# Power_USB.net
KiCad netlist of a schematic drawn in Altium Designer
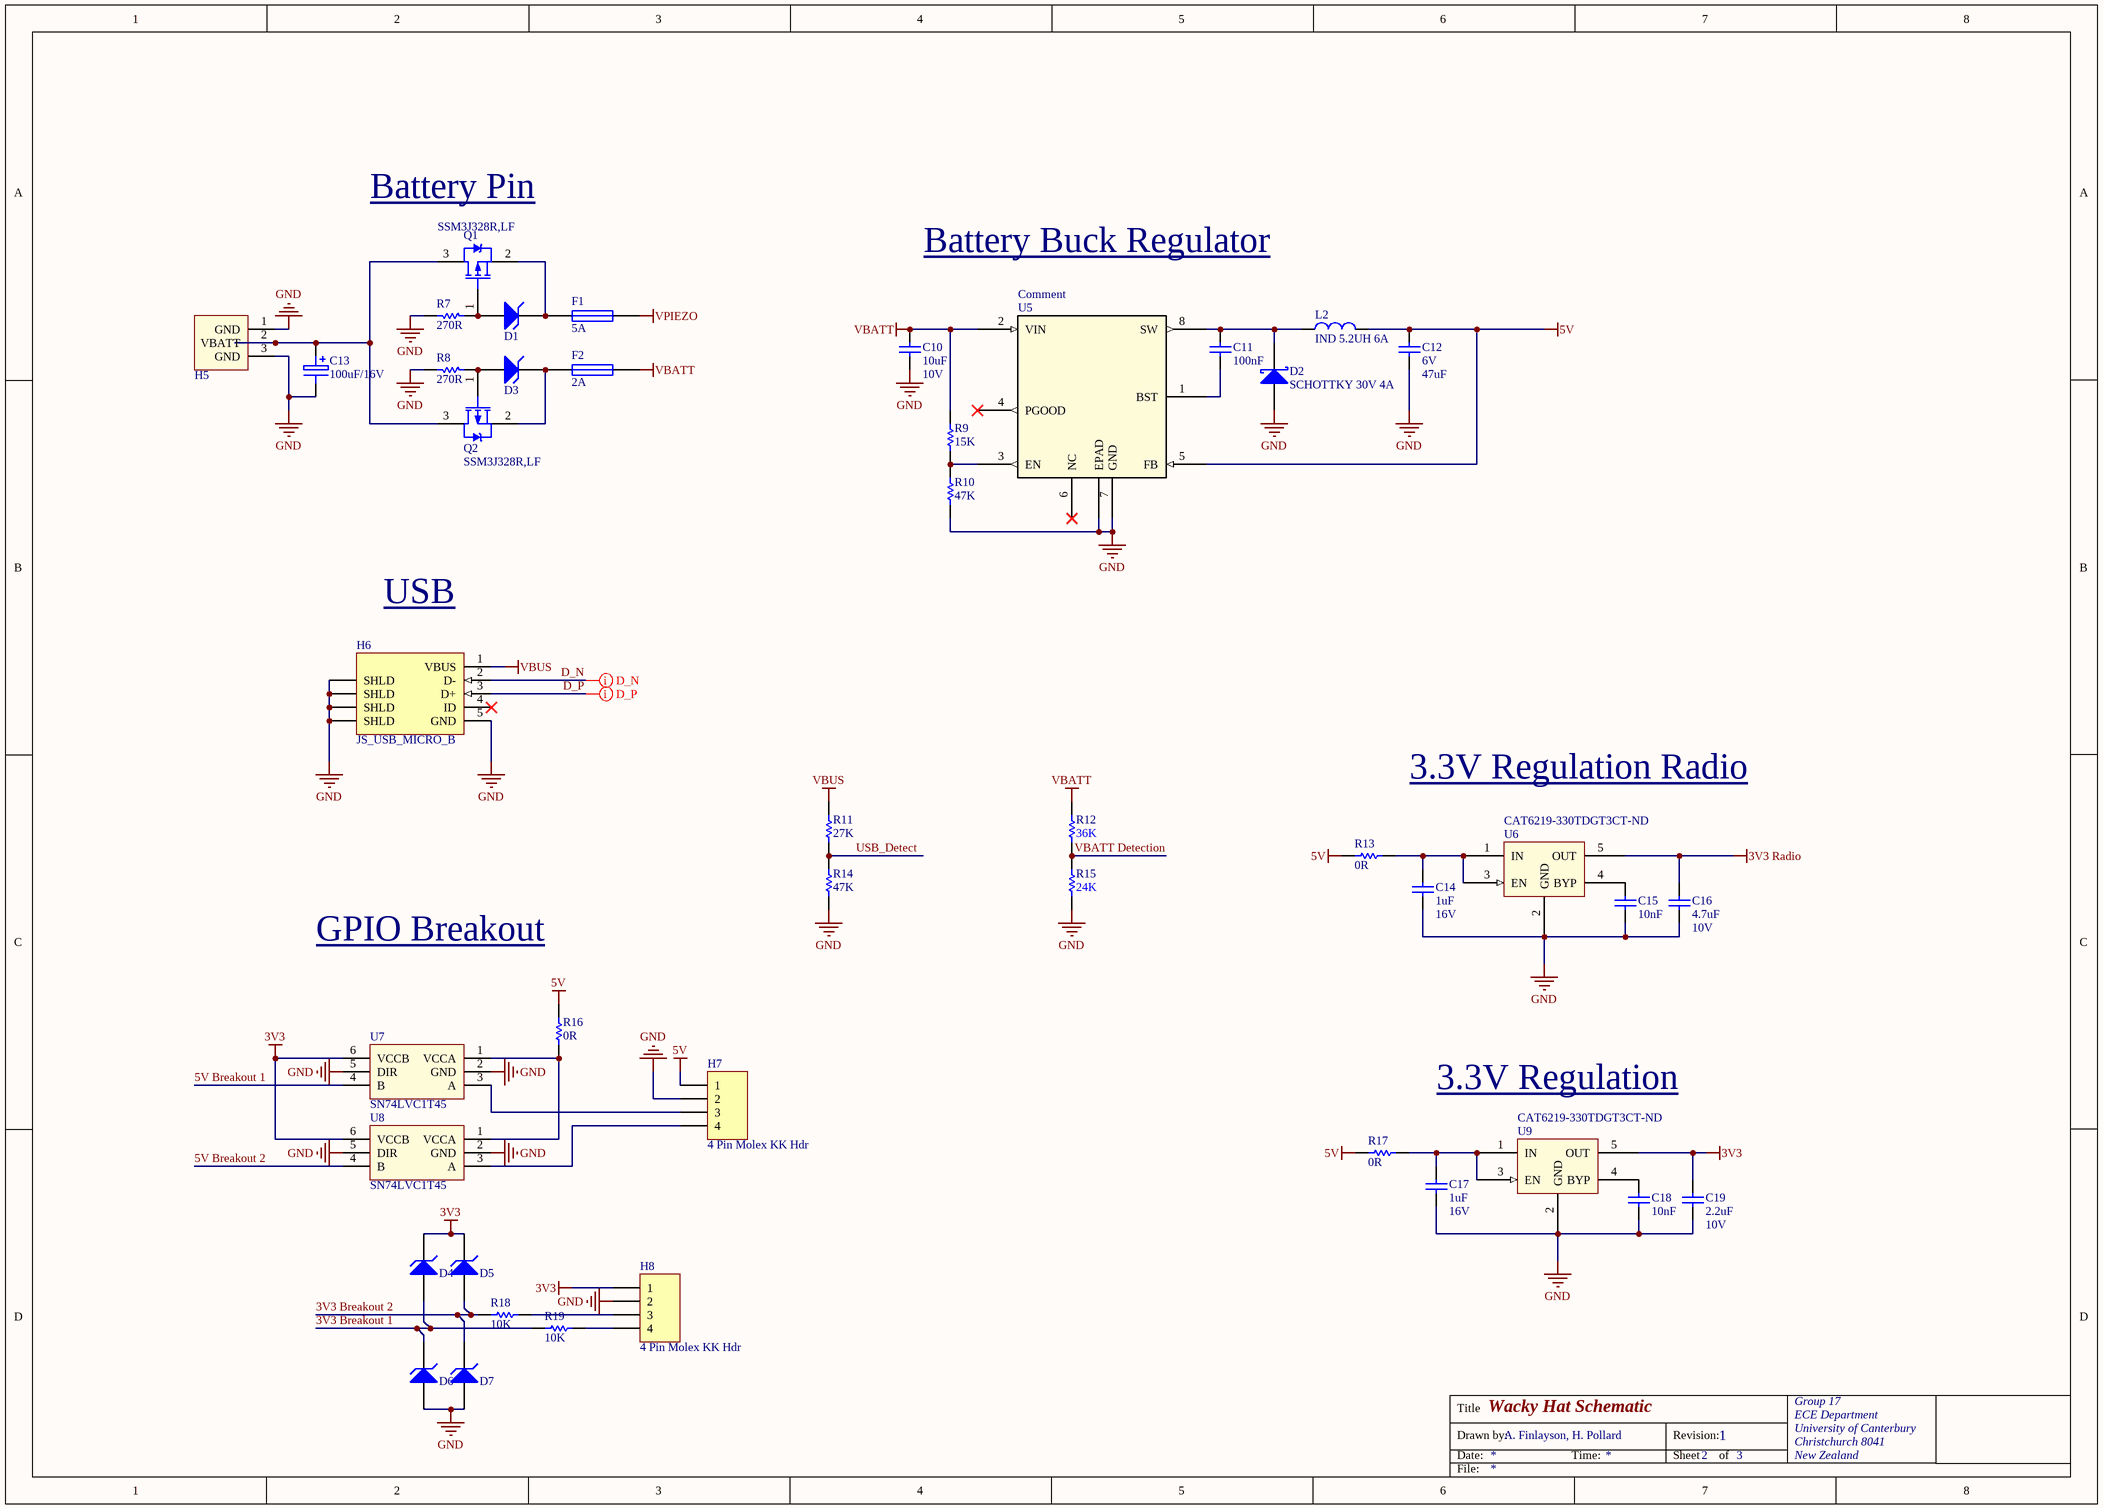
[diagram p0: Power_USB.SchDoc]

(export (version "E")
  (design (tool "Eeschema 10.0.6"))
  (components
    (comp (ref "C10")
      (value "10uF")
      (footprint "CAPC2012L")
      (description "CAP CER 10uF X7R +-20% 10V 0805")
      (fields (field (name "MAX VOLTAGE") "10V"))
      (libsource (lib "ECE AD19Components_19V1") (part "CC_10uF_0805_10V"))
    )
    (comp (ref "C11")
      (value "100nF")
      (footprint "CAPC1608L")
      (description "CAP CER 100nF X7R +-10% 50V 0603")
      (libsource (lib "ECE AD19Components_19V1") (part "CC_100nF_0603"))
    )
    (comp (ref "C12")
      (value "47uF")
      (footprint "CAPC3216L")
      (description "CAP CER 47uF X5R -/+20% 6V 1206")
      (fields (field (name "MAX VOLTAGE") "6V"))
      (libsource (lib "ECE AD19Components_19V1") (part "CC_47uF_1206"))
    )
    (comp (ref "C13")
      (value "100uF/16V")
      (footprint "NICH-1")
      (description "CAP ALUM 100uF 16V SMD")
      (fields (field (name "MANUFACTURER") "Nichcon"))
      (libsource (lib "ECE AD19Components_19V1") (part "CA_100uF_16V"))
    )
    (comp (ref "C14")
      (value "1uF")
      (footprint "CAPC1608L")
      (description "CAP CER 1uF Y5V -20% +80% 16V 0603")
      (fields (field (name "MAX VOLTAGE") "16V"))
      (libsource (lib "ECE AD19Components_19V1") (part "CC_1uF_0603"))
    )
    (comp (ref "C15")
      (value "10nF")
      (footprint "CAPC1608L")
      (description "CAP CER 10nF X7R +-10% 50V 0603")
      (libsource (lib "ECE AD19Components_19V1") (part "CC_10nF_0603"))
    )
    (comp (ref "C16")
      (value "4.7uF")
      (footprint "CAPC1608N")
      (description "CAP CER 4.7uF X5R +-20%  10V 0603")
      (fields (field (name "MAX VOLTAGE") "10V"))
      (libsource (lib "ECE AD19Components_19V1") (part "CC_4.7uF_0603"))
    )
    (comp (ref "C17")
      (value "1uF")
      (footprint "CAPC1608L")
      (description "CAP CER 1uF Y5V -20% +80% 16V 0603")
      (fields (field (name "MAX VOLTAGE") "16V"))
      (libsource (lib "ECE AD19Components_19V1") (part "CC_1uF_0603"))
    )
    (comp (ref "C18")
      (value "10nF")
      (footprint "CAPC1608L")
      (description "CAP CER 10nF X7R +-10% 50V 0603")
      (libsource (lib "ECE AD19Components_19V1") (part "CC_10nF_0603"))
    )
    (comp (ref "C19")
      (value "2.2uF")
      (footprint "CAPC1608L")
      (description "CAP CER 2.2uF X5R +-20% 10V 0603")
      (fields (field (name "MAX VOLTAGE") "10V"))
      (libsource (lib "ECE AD19Components_19V1") (part "CC_2.2uF_0603"))
    )
    (comp (ref "D1")
      (value "DIODE ZENER 5.6V")
      (footprint "DO-214AA_SCL")
      (description "DIODE ZENER 5.6V 5W DO214AA")
      (fields
        (field (name "MANUFACTURER") "Micro Commercial Co")
        (field (name "MANUFACTURER PART NUMBER") "SMBJ5339B-TP")
      )
      (libsource (lib "ENCE461AD19_19V2") (part "SMBJ5339B-TP"))
    )
    (comp (ref "D2")
      (value "SCHOTTKY 30V 4A")
      (footprint "SMC")
      (description "DIODE SCHOTTKY 30V 4A SMC")
      (fields
        (field (name "MANUFACTURER") "ON Semiconductor")
        (field (name "MANUFACTURER PART NUMBER") "MBRS330T3G")
      )
      (libsource (lib "ENCE461AD19_19V2") (part "MBRS330T3G"))
    )
    (comp (ref "D3")
      (value "DIODE ZENER 5.6V")
      (footprint "DO-214AA_SCL")
      (description "DIODE ZENER 5.6V 5W DO214AA")
      (fields
        (field (name "MANUFACTURER") "Micro Commercial Co")
        (field (name "MANUFACTURER PART NUMBER") "SMBJ5339B-TP")
      )
      (libsource (lib "ENCE461AD19_19V2") (part "SMBJ5339B-TP"))
    )
    (comp (ref "D4")
      (value "DIODE ZENER 5.6V")
      (footprint "DO-214AA_SCL")
      (description "DIODE ZENER 5.6V 5W DO214AA")
      (fields
        (field (name "MANUFACTURER") "Micro Commercial Co")
        (field (name "MANUFACTURER PART NUMBER") "SMBJ5339B-TP")
      )
      (libsource (lib "ENCE461AD19_19V2") (part "SMBJ5339B-TP"))
    )
    (comp (ref "D5")
      (value "DIODE ZENER 5.6V")
      (footprint "DO-214AA_SCL")
      (description "DIODE ZENER 5.6V 5W DO214AA")
      (fields
        (field (name "MANUFACTURER") "Micro Commercial Co")
        (field (name "MANUFACTURER PART NUMBER") "SMBJ5339B-TP")
      )
      (libsource (lib "ENCE461AD19_19V2") (part "SMBJ5339B-TP"))
    )
    (comp (ref "D6")
      (value "DIODE ZENER 5.6V")
      (footprint "DO-214AA_SCL")
      (description "DIODE ZENER 5.6V 5W DO214AA")
      (fields
        (field (name "MANUFACTURER") "Micro Commercial Co")
        (field (name "MANUFACTURER PART NUMBER") "SMBJ5339B-TP")
      )
      (libsource (lib "ENCE461AD19_19V2") (part "SMBJ5339B-TP"))
    )
    (comp (ref "D7")
      (value "DIODE ZENER 5.6V")
      (footprint "DO-214AA_SCL")
      (description "DIODE ZENER 5.6V 5W DO214AA")
      (fields
        (field (name "MANUFACTURER") "Micro Commercial Co")
        (field (name "MANUFACTURER PART NUMBER") "SMBJ5339B-TP")
      )
      (libsource (lib "ENCE461AD19_19V2") (part "SMBJ5339B-TP"))
    )
    (comp (ref "F1")
      (value "5A")
      (footprint "RESC3216N")
      (description "Fuse 5.0A Fast Acting 1206 SMD")
      (fields (field (name "MANUFACTURER PART NUMBER") "C1F5") (field (name "MANUFACTURER") "Bel TRP"))
      (libsource (lib "ECE AD19Components_19V1") (part "FS_Fuse_5.0A"))
    )
    (comp (ref "F2")
      (value "2A")
      (footprint "RESC3216N")
      (description "Fuse 2.0A Very Fast Acting 1206 SMD")
      (fields
        (field (name "MANUFACTURER") "MULTICOMP")
        (field (name "MANUFACTURER PART NUMBER") "MC12CF 002")
      )
      (libsource (lib "ECE AD19Components_19V1") (part "FS_Fuse_2.0A"))
    )
    (comp (ref "H5")
      (value "Battery_HEADER_3pin")
      (footprint "BATT_HEADER_3POS")
      (description "3Pin Header 2.54mm spacing")
      (libsource (lib "ENCE461AD19_19V2") (part "Battery_HEADER_3pin"))
    )
    (comp (ref "H6")
      (value "JS_USB_MICRO_B")
      (footprint "FCI_USB_10118194-0001LF")
      (description "CONN USB MICRO B RECPT SMT R/A")
      (fields (field (name "MANUFACTURER") "FCI") (field (name "MANUFACTURER PART NUMBER") "10118194-0001LF"))
      (libsource (lib "ECE AD19Components_19V1") (part "JS_USB_MICRO_B_SMT"))
    )
    (comp (ref "H7")
      (value "4 Pin Molex KK Hdr")
      (footprint "MOLEX_KK_4_HDR")
      (description "CONN HEADER 4POS 2.54mm VERT_Thru Hole")
      (fields (field (name "MANUFACTURER") "Molex"))
      (libsource (lib "ECE AD19Components_19V1") (part "JA_MOLEX_KK_4POS"))
    )
    (comp (ref "H8")
      (value "4 Pin Molex KK Hdr")
      (footprint "MOLEX_KK_4_HDR")
      (description "CONN HEADER 4POS 2.54mm VERT_Thru Hole")
      (fields (field (name "MANUFACTURER") "Molex"))
      (libsource (lib "ECE AD19Components_19V1") (part "JA_MOLEX_KK_4POS"))
    )
    (comp (ref "L2")
      (value "IND 5.2UH 6A")
      (footprint "INDUCTOR5u2")
      (description "FIXED IND 5.2UH 6A 22 MOHM SMD")
      (fields
        (field (name "MANUFACTURER") "Sumida America Components Inc.")
        (field (name "MANUFACTURER PART NUMBER") "CDRH104RNP-5R2NC")
      )
      (libsource (lib "ENCE461AD19_19V2") (part "CDRH104RNP-5R2NC"))
    )
    (comp (ref "Q1")
      (value "SSM3J328R,LF")
      (footprint "SOT23_L")
      (description "MOSFET P-CH 20V 6A SOT23-3")
      (fields
        (field (name "MANUFACTURER") "Toshiba")
        (field (name "MANUFACTURER PART NUMBER") "SSM3J328R,LF")
      )
      (libsource (lib "ECE AD19Components_19V1") (part "TM_SSM3J328R"))
    )
    (comp (ref "Q2")
      (value "SSM3J328R,LF")
      (footprint "SOT23_L")
      (description "MOSFET P-CH 20V 6A SOT23-3")
      (fields
        (field (name "MANUFACTURER") "Toshiba")
        (field (name "MANUFACTURER PART NUMBER") "SSM3J328R,LF")
      )
      (libsource (lib "ECE AD19Components_19V1") (part "TM_SSM3J328R"))
    )
    (comp (ref "R7")
      (value "270R")
      (footprint "RESC1608L")
      (description "RES 270 OHM 1/10W 5% 0603 SMD")
      (libsource (lib "ECE AD19Components_19V1") (part "RS_270R"))
    )
    (comp (ref "R8")
      (value "270R")
      (footprint "RESC1608L")
      (description "RES 270 OHM 1/10W 5% 0603 SMD")
      (libsource (lib "ECE AD19Components_19V1") (part "RS_270R"))
    )
    (comp (ref "R9")
      (value "15K")
      (footprint "RESC1608L")
      (description "RES 15.0K OHM 1/10W 5% 0603 SMD")
      (libsource (lib "ECE AD19Components_19V1") (part "RS_15K"))
    )
    (comp (ref "R10")
      (value "47K")
      (footprint "RESC1608N")
      (description "RES 47.0K OHM 1/10W 5% 0603 SMD")
      (libsource (lib "ECE AD19Components_19V1") (part "RS_47K"))
    )
    (comp (ref "R11")
      (value "27K")
      (footprint "RESC1608L")
      (description "RES 27K OHM 1/10W 5% 0603 SMD")
      (libsource (lib "ECE AD19Components_19V1") (part "RS_27K"))
    )
    (comp (ref "R12")
      (value "36K")
      (footprint "RESC1608L")
      (description "RES 36K OHM 1/10W 5% 0603 SMD")
      (libsource (lib "ECE AD19Components_19V1") (part "RS_36K"))
    )
    (comp (ref "R13")
      (value "0R")
      (footprint "RESC1608L")
      (description "RES 0.0 OHM 1/10W 5% 0603 SMD")
      (libsource (lib "ECE AD19Components_19V1") (part "RS_0R0"))
    )
    (comp (ref "R14")
      (value "47K")
      (footprint "RESC1608L")
      (description "RES 47.0K OHM 1/10W 5% 0603 SMD")
      (libsource (lib "ECE AD19Components_19V1") (part "RS_47K"))
    )
    (comp (ref "R15")
      (value "24K")
      (footprint "RESC1608L")
      (description "RES 24K OHM 1/10W 5% 0603 SMD")
      (libsource (lib "ECE AD19Components_19V1") (part "RS_24K"))
    )
    (comp (ref "R16")
      (value "0R")
      (footprint "RESC1608L")
      (description "RES 0.0 OHM 1/10W 5% 0603 SMD")
      (libsource (lib "ECE AD19Components_19V1") (part "RS_0R0"))
    )
    (comp (ref "R17")
      (value "0R")
      (footprint "RESC1608L")
      (description "RES 0.0 OHM 1/10W 5% 0603 SMD")
      (libsource (lib "ECE AD19Components_19V1") (part "RS_0R0"))
    )
    (comp (ref "R18")
      (value "10K")
      (footprint "RESC1608L")
      (description "RES 10.0K OHM 1/10W 5% 0603 SMD")
      (libsource (lib "ECE AD19Components_19V1") (part "RS_10K"))
    )
    (comp (ref "R19")
      (value "10K")
      (footprint "RESC1608L")
      (description "RES 10.0K OHM 1/10W 5% 0603 SMD")
      (libsource (lib "ECE AD19Components_19V1") (part "RS_10K"))
    )
    (comp (ref "U5")
      (value "Comment")
      (footprint "RD_8_1")
      (description "IC REG BUCK 5V 2A 8SOIC")
      (fields (field (name "MANUFACTURER_PART_NUMBER") "ADP2302ARDZ-5.0-R7"))
      (libsource (lib "ENCE461AD19_19V2") (part "ADP2302ARDZ-5.0-R7"))
    )
    (comp (ref "U6")
      (value "CAT6219-330TDGT3")
      (footprint "SOT95P280X145-5N")
      (description "IC REG LIN 3.3V 500MA TSOT23-5")
      (fields
        (field (name "BASE PART NUMBER") "CAT6219")
        (field (name "SUPPLIER PART NUMBER") "CAT6219-330TDGT3CT-ND")
      )
      (libsource (lib "ENCE461AD19_19V2") (part "SV_CAT6219-330TDGT3"))
    )
    (comp (ref "U7")
      (value "SN74LVC1T45")
      (footprint "SOT23-6_N")
      (description "1.8V - 5V level converter")
      (libsource (lib "ENCE461_extras_2020") (part "SN74LVC1T45"))
    )
    (comp (ref "U8")
      (value "SN74LVC1T45")
      (footprint "SOT23-6_N")
      (description "1.8V - 5V level converter")
      (libsource (lib "ENCE461_extras_2020") (part "SN74LVC1T45"))
    )
    (comp (ref "U9")
      (value "CAT6219-330TDGT3")
      (footprint "SOT95P280X145-5N")
      (description "IC REG LIN 3.3V 500MA TSOT23-5")
      (fields
        (field (name "BASE PART NUMBER") "CAT6219")
        (field (name "SUPPLIER PART NUMBER") "CAT6219-330TDGT3CT-ND")
      )
      (libsource (lib "ENCE461AD19_19V2") (part "SV_CAT6219-330TDGT3"))
    )
  )
  (nets
    (net (code "1") (name "/3V3 Breakout 1") (class "Default")
      (node (ref "D4") (pin "2") (pinfunction "A_2") (pintype "passive"))
      (node (ref "D6") (pin "1") (pinfunction "K_1") (pintype "passive"))
      (node (ref "R19") (pin "1") (pinfunction "1_1") (pintype "passive"))
    )
    (net (code "2") (name "/3V3 Breakout 2") (class "Default")
      (node (ref "D5") (pin "2") (pinfunction "A_2") (pintype "passive"))
      (node (ref "D7") (pin "1") (pinfunction "K_1") (pintype "passive"))
      (node (ref "R18") (pin "1") (pinfunction "1_1") (pintype "passive"))
    )
    (net (code "3") (name "/5V Breakout 1") (class "Default")
      (node (ref "U7") (pin "4") (pinfunction "B_4") (pintype "passive"))
    )
    (net (code "4") (name "/5V Breakout 2") (class "Default")
      (node (ref "U8") (pin "4") (pinfunction "B_4") (pintype "passive"))
    )
    (net (code "5") (name "/D_N") (class "Default")
      (node (ref "H6") (pin "2") (pinfunction "D-_2") (pintype "input"))
    )
    (net (code "6") (name "/D_P") (class "Default")
      (node (ref "H6") (pin "3") (pinfunction "D+_3") (pintype "input"))
    )
    (net (code "7") (name "/USB_Detect") (class "Default")
      (node (ref "R11") (pin "1") (pinfunction "1_1") (pintype "passive"))
      (node (ref "R14") (pin "2") (pinfunction "2_2") (pintype "passive"))
    )
    (net (code "8") (name "/VBATT Detection") (class "Default")
      (node (ref "R12") (pin "1") (pinfunction "1_1") (pintype "passive"))
      (node (ref "R15") (pin "2") (pinfunction "2_2") (pintype "passive"))
    )
    (net (code "9") (name "3V3") (class "Default")
      (node (ref "C19") (pin "2") (pinfunction "2_2") (pintype "passive"))
      (node (ref "D4") (pin "1") (pinfunction "K_1") (pintype "passive"))
      (node (ref "D5") (pin "1") (pinfunction "K_1") (pintype "passive"))
      (node (ref "H8") (pin "1") (pinfunction "1_1") (pintype "passive"))
      (node (ref "U7") (pin "6") (pinfunction "VCCB_6") (pintype "passive"))
      (node (ref "U8") (pin "6") (pinfunction "VCCB_6") (pintype "passive"))
      (node (ref "U9") (pin "5") (pinfunction "OUT_5") (pintype "power_in"))
    )
    (net (code "10") (name "3V3 Radio") (class "Default")
      (node (ref "C16") (pin "2") (pinfunction "2_2") (pintype "passive"))
      (node (ref "U6") (pin "5") (pinfunction "OUT_5") (pintype "power_in"))
    )
    (net (code "11") (name "5V") (class "Default")
      (node (ref "C12") (pin "2") (pinfunction "2_2") (pintype "passive"))
      (node (ref "H7") (pin "1") (pinfunction "1_1") (pintype "passive"))
      (node (ref "L2") (pin "2") (pintype "passive"))
      (node (ref "R13") (pin "1") (pinfunction "1_1") (pintype "passive"))
      (node (ref "R16") (pin "2") (pinfunction "2_2") (pintype "passive"))
      (node (ref "R17") (pin "1") (pinfunction "1_1") (pintype "passive"))
      (node (ref "U5") (pin "5") (pinfunction "FB_5") (pintype "input"))
    )
    (net (code "12") (name "GND") (class "Default")
      (node (ref "C10") (pin "1") (pinfunction "1_1") (pintype "passive"))
      (node (ref "C12") (pin "1") (pinfunction "1_1") (pintype "passive"))
      (node (ref "C13") (pin "1") (pintype "passive"))
      (node (ref "C14") (pin "1") (pinfunction "1_1") (pintype "passive"))
      (node (ref "C15") (pin "1") (pinfunction "1_1") (pintype "passive"))
      (node (ref "C16") (pin "1") (pinfunction "1_1") (pintype "passive"))
      (node (ref "C17") (pin "1") (pinfunction "1_1") (pintype "passive"))
      (node (ref "C18") (pin "1") (pinfunction "1_1") (pintype "passive"))
      (node (ref "C19") (pin "1") (pinfunction "1_1") (pintype "passive"))
      (node (ref "D2") (pin "1") (pinfunction "A_1") (pintype "passive"))
      (node (ref "D6") (pin "2") (pinfunction "A_2") (pintype "passive"))
      (node (ref "D7") (pin "2") (pinfunction "A_2") (pintype "passive"))
      (node (ref "H5") (pin "1") (pinfunction "GND_1") (pintype "passive"))
      (node (ref "H5") (pin "3") (pinfunction "GND_3") (pintype "passive"))
      (node (ref "H6") (pin "5") (pinfunction "GND_5") (pintype "passive"))
      (node (ref "H6") (pin "6") (pinfunction "SHLD_6") (pintype "passive"))
      (node (ref "H7") (pin "2") (pinfunction "2_2") (pintype "passive"))
      (node (ref "H8") (pin "2") (pinfunction "2_2") (pintype "passive"))
      (node (ref "R10") (pin "1") (pinfunction "1_1") (pintype "passive"))
      (node (ref "R14") (pin "1") (pinfunction "1_1") (pintype "passive"))
      (node (ref "R15") (pin "1") (pinfunction "1_1") (pintype "passive"))
      (node (ref "R7") (pin "1") (pinfunction "1_1") (pintype "passive"))
      (node (ref "R8") (pin "1") (pinfunction "1_1") (pintype "passive"))
      (node (ref "U5") (pin "7") (pinfunction "GND_7") (pintype "power_in"))
      (node (ref "U5") (pin "EPAD") (pinfunction "EPAD_EPAD") (pintype "passive"))
      (node (ref "U6") (pin "2") (pinfunction "GND_2") (pintype "power_in"))
      (node (ref "U7") (pin "2") (pinfunction "GND_2") (pintype "passive"))
      (node (ref "U7") (pin "5") (pinfunction "DIR_5") (pintype "passive"))
      (node (ref "U8") (pin "2") (pinfunction "GND_2") (pintype "passive"))
      (node (ref "U8") (pin "5") (pinfunction "DIR_5") (pintype "passive"))
      (node (ref "U9") (pin "2") (pinfunction "GND_2") (pintype "power_in"))
    )
    (net (code "13") (name "Net-(D1-A)") (class "Default")
      (node (ref "D1") (pin "2") (pinfunction "A_2") (pintype "passive"))
      (node (ref "Q1") (pin "1") (pinfunction "1_1") (pintype "passive"))
      (node (ref "R7") (pin "2") (pinfunction "2_2") (pintype "passive"))
    )
    (net (code "14") (name "Net-(D1-K)") (class "Default")
      (node (ref "D1") (pin "1") (pinfunction "K_1") (pintype "passive"))
      (node (ref "F1") (pin "1") (pinfunction "1_1") (pintype "passive"))
      (node (ref "Q1") (pin "2") (pinfunction "2_2") (pintype "passive"))
    )
    (net (code "15") (name "Net-(D2-K)") (class "Default")
      (node (ref "C11") (pin "2") (pinfunction "2_2") (pintype "passive"))
      (node (ref "D2") (pin "2") (pinfunction "K_2") (pintype "passive"))
      (node (ref "L2") (pin "1") (pintype "passive"))
      (node (ref "U5") (pin "8") (pinfunction "SW_8") (pintype "output"))
    )
    (net (code "16") (name "Net-(D3-A)") (class "Default")
      (node (ref "D3") (pin "2") (pinfunction "A_2") (pintype "passive"))
      (node (ref "Q2") (pin "1") (pinfunction "1_1") (pintype "passive"))
      (node (ref "R8") (pin "2") (pinfunction "2_2") (pintype "passive"))
    )
    (net (code "17") (name "Net-(D3-K)") (class "Default")
      (node (ref "D3") (pin "1") (pinfunction "K_1") (pintype "passive"))
      (node (ref "F2") (pin "1") (pinfunction "1_1") (pintype "passive"))
      (node (ref "Q2") (pin "2") (pinfunction "2_2") (pintype "passive"))
    )
    (net (code "18") (name "Net-(H5-VBATT)") (class "Default")
      (node (ref "C13") (pin "2") (pintype "passive"))
      (node (ref "H5") (pin "2") (pinfunction "VBATT_2") (pintype "passive"))
      (node (ref "Q1") (pin "3") (pinfunction "3_3") (pintype "passive"))
      (node (ref "Q2") (pin "3") (pinfunction "3_3") (pintype "passive"))
    )
    (net (code "19") (name "Net-(H8-Pad3)") (class "Default")
      (node (ref "H8") (pin "3") (pinfunction "3_3") (pintype "passive"))
      (node (ref "R18") (pin "2") (pinfunction "2_2") (pintype "passive"))
    )
    (net (code "20") (name "Net-(H8-Pad4)") (class "Default")
      (node (ref "H8") (pin "4") (pinfunction "4_4") (pintype "passive"))
      (node (ref "R19") (pin "2") (pinfunction "2_2") (pintype "passive"))
    )
    (net (code "21") (name "Net-(U5-BST)") (class "Default")
      (node (ref "C11") (pin "1") (pinfunction "1_1") (pintype "passive"))
      (node (ref "U5") (pin "1") (pinfunction "BST_1") (pintype "passive"))
    )
    (net (code "22") (name "Net-(U5-EN)") (class "Default")
      (node (ref "R10") (pin "2") (pinfunction "2_2") (pintype "passive"))
      (node (ref "R9") (pin "1") (pinfunction "1_1") (pintype "passive"))
      (node (ref "U5") (pin "3") (pinfunction "EN_3") (pintype "output"))
    )
    (net (code "23") (name "Net-(U6-BYP)") (class "Default")
      (node (ref "C15") (pin "2") (pinfunction "2_2") (pintype "passive"))
      (node (ref "U6") (pin "4") (pinfunction "BYP_4") (pintype "passive"))
    )
    (net (code "24") (name "Net-(U6-EN)") (class "Default")
      (node (ref "C14") (pin "2") (pinfunction "2_2") (pintype "passive"))
      (node (ref "R13") (pin "2") (pinfunction "2_2") (pintype "passive"))
      (node (ref "U6") (pin "1") (pinfunction "IN_1") (pintype "power_in"))
      (node (ref "U6") (pin "3") (pinfunction "EN_3") (pintype "input"))
    )
    (net (code "25") (name "Net-(U7-A)") (class "Default")
      (node (ref "H7") (pin "3") (pinfunction "3_3") (pintype "passive"))
      (node (ref "U7") (pin "3") (pinfunction "A_3") (pintype "passive"))
    )
    (net (code "26") (name "Net-(U7-VCCA)") (class "Default")
      (node (ref "R16") (pin "1") (pinfunction "1_1") (pintype "passive"))
      (node (ref "U7") (pin "1") (pinfunction "VCCA_1") (pintype "passive"))
      (node (ref "U8") (pin "1") (pinfunction "VCCA_1") (pintype "passive"))
    )
    (net (code "27") (name "Net-(U8-A)") (class "Default")
      (node (ref "H7") (pin "4") (pinfunction "4_4") (pintype "passive"))
      (node (ref "U8") (pin "3") (pinfunction "A_3") (pintype "passive"))
    )
    (net (code "28") (name "Net-(U9-BYP)") (class "Default")
      (node (ref "C18") (pin "2") (pinfunction "2_2") (pintype "passive"))
      (node (ref "U9") (pin "4") (pinfunction "BYP_4") (pintype "passive"))
    )
    (net (code "29") (name "Net-(U9-EN)") (class "Default")
      (node (ref "C17") (pin "2") (pinfunction "2_2") (pintype "passive"))
      (node (ref "R17") (pin "2") (pinfunction "2_2") (pintype "passive"))
      (node (ref "U9") (pin "1") (pinfunction "IN_1") (pintype "power_in"))
      (node (ref "U9") (pin "3") (pinfunction "EN_3") (pintype "input"))
    )
    (net (code "30") (name "VBATT") (class "Default")
      (node (ref "C10") (pin "2") (pinfunction "2_2") (pintype "passive"))
      (node (ref "F2") (pin "2") (pinfunction "2_2") (pintype "passive"))
      (node (ref "R12") (pin "2") (pinfunction "2_2") (pintype "passive"))
      (node (ref "R9") (pin "2") (pinfunction "2_2") (pintype "passive"))
      (node (ref "U5") (pin "2") (pinfunction "VIN_2") (pintype "input"))
    )
    (net (code "31") (name "VBUS") (class "Default")
      (node (ref "H6") (pin "1") (pinfunction "VBUS_1") (pintype "power_in"))
      (node (ref "R11") (pin "2") (pinfunction "2_2") (pintype "passive"))
    )
    (net (code "32") (name "VPIEZO") (class "Default")
      (node (ref "F1") (pin "2") (pinfunction "2_2") (pintype "passive"))
    )
    (net (code "33") (name "unconnected-(H6-ID-Pad4)") (class "Default")
      (node (ref "H6") (pin "4") (pinfunction "ID_4") (pintype "power_in+no_connect"))
    )
    (net (code "34") (name "unconnected-(U5-NC-Pad6)") (class "Default")
      (node (ref "U5") (pin "6") (pinfunction "NC_6") (pintype "passive+no_connect"))
    )
    (net (code "35") (name "unconnected-(U5-PGOOD-Pad4)") (class "Default")
      (node (ref "U5") (pin "4") (pinfunction "PGOOD_4") (pintype "output+no_connect"))
    )
  )
)
